# bai_1.net
KiCad netlist of a schematic drawn in Altium Designer
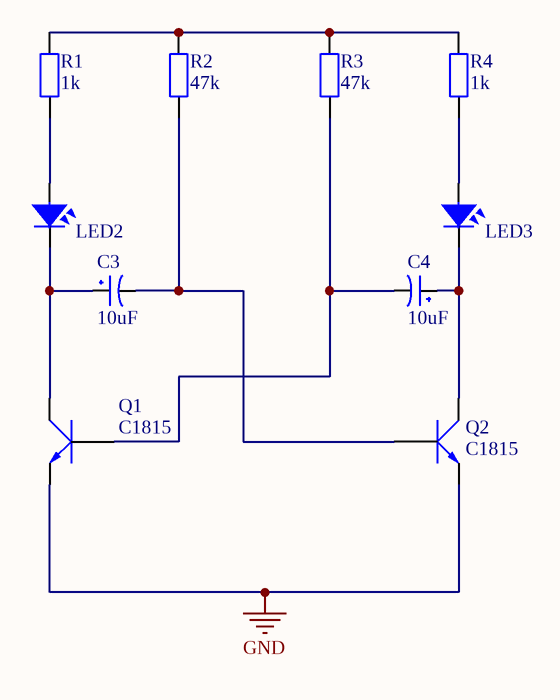
[diagram p0: bai 1.SchDoc]

(export (version "E")
  (design (tool "Eeschema 10.0.6"))
  (components
    (comp (ref "C3")
      (value "10uF")
      (footprint "tu hoa 4mm")
      (description "Cắm")
      (libsource (lib "Tu dien") (part "Tu Hoa 10uF 16V 4x7"))
    )
    (comp (ref "C4")
      (value "10uF")
      (footprint "tu hoa 4mm")
      (description "Cắm")
      (libsource (lib "Tu dien") (part "Tu Hoa 10uF 16V 4x7"))
    )
    (comp (ref "LED2")
      (value "LED")
      (footprint "LED-3")
      (description "LED Single colour Green and Red")
      (libsource (lib "syhaunguyen") (part "LED"))
    )
    (comp (ref "LED3")
      (value "LED")
      (footprint "LED-3")
      (description "LED Single colour Green and Red")
      (libsource (lib "syhaunguyen") (part "LED"))
    )
    (comp (ref "Q1")
      (value "C1815")
      (footprint "TO92")
      (description "NPN transistor")
      (libsource (lib "TranFet") (part "C1815"))
    )
    (comp (ref "Q2")
      (value "C1815")
      (footprint "TO92")
      (description "NPN transistor")
      (libsource (lib "TranFet") (part "C1815"))
    )
    (comp (ref "R1")
      (value "1k")
      (footprint "tro vach 1/4w")
      (description "Cắm")
      (libsource (lib "Dien Tro") (part "Tro Vach 1/4W 5% 2k"))
    )
    (comp (ref "R2")
      (value "47k")
      (footprint "tro vach 1/4w")
      (description "Cắm")
      (libsource (lib "Dien Tro") (part "Tro Vach 1/4W 5% 2k"))
    )
    (comp (ref "R3")
      (value "47k")
      (footprint "tro vach 1/4w")
      (description "Cắm")
      (libsource (lib "Dien Tro") (part "Tro Vach 1/4W 5% 2k"))
    )
    (comp (ref "R4")
      (value "1k")
      (footprint "tro vach 1/4w")
      (description "Cắm")
      (libsource (lib "Dien Tro") (part "Tro Vach 1/4W 5% 2k"))
    )
  )
  (nets
    (net (code "1") (name "GND") (class "Default")
      (node (ref "Q1") (pin "1") (pinfunction "E_1") (pintype "passive"))
      (node (ref "Q2") (pin "1") (pinfunction "E_1") (pintype "passive"))
    )
    (net (code "2") (name "Net-(LED2-Pad1)") (class "Default")
      (node (ref "LED2") (pin "1") (pinfunction "1_1") (pintype "passive"))
      (node (ref "R1") (pin "1") (pinfunction "1_1") (pintype "passive"))
    )
    (net (code "3") (name "Net-(LED3-Pad1)") (class "Default")
      (node (ref "LED3") (pin "1") (pinfunction "1_1") (pintype "passive"))
      (node (ref "R4") (pin "1") (pinfunction "1_1") (pintype "passive"))
    )
    (net (code "4") (name "Net-(Q1-B)") (class "Default")
      (node (ref "C4") (pin "2") (pinfunction "2_2") (pintype "passive"))
      (node (ref "Q1") (pin "3") (pinfunction "B_3") (pintype "passive"))
      (node (ref "R3") (pin "1") (pinfunction "1_1") (pintype "passive"))
    )
    (net (code "5") (name "Net-(Q1-C)") (class "Default")
      (node (ref "C3") (pin "1") (pinfunction "1_1") (pintype "passive"))
      (node (ref "LED2") (pin "2") (pinfunction "2_2") (pintype "passive"))
      (node (ref "Q1") (pin "2") (pinfunction "C_2") (pintype "passive"))
    )
    (net (code "6") (name "Net-(Q2-B)") (class "Default")
      (node (ref "C3") (pin "2") (pinfunction "2_2") (pintype "passive"))
      (node (ref "Q2") (pin "3") (pinfunction "B_3") (pintype "passive"))
      (node (ref "R2") (pin "1") (pinfunction "1_1") (pintype "passive"))
    )
    (net (code "7") (name "Net-(Q2-C)") (class "Default")
      (node (ref "C4") (pin "1") (pinfunction "1_1") (pintype "passive"))
      (node (ref "LED3") (pin "2") (pinfunction "2_2") (pintype "passive"))
      (node (ref "Q2") (pin "2") (pinfunction "C_2") (pintype "passive"))
    )
    (net (code "8") (name "Net-(R1-Pad2)") (class "Default")
      (node (ref "R1") (pin "2") (pinfunction "2_2") (pintype "passive"))
      (node (ref "R2") (pin "2") (pinfunction "2_2") (pintype "passive"))
      (node (ref "R3") (pin "2") (pinfunction "2_2") (pintype "passive"))
      (node (ref "R4") (pin "2") (pinfunction "2_2") (pintype "passive"))
    )
  )
)
